# GMSL_SERIALIZER.net
KiCad netlist of a schematic drawn in Altium Designer
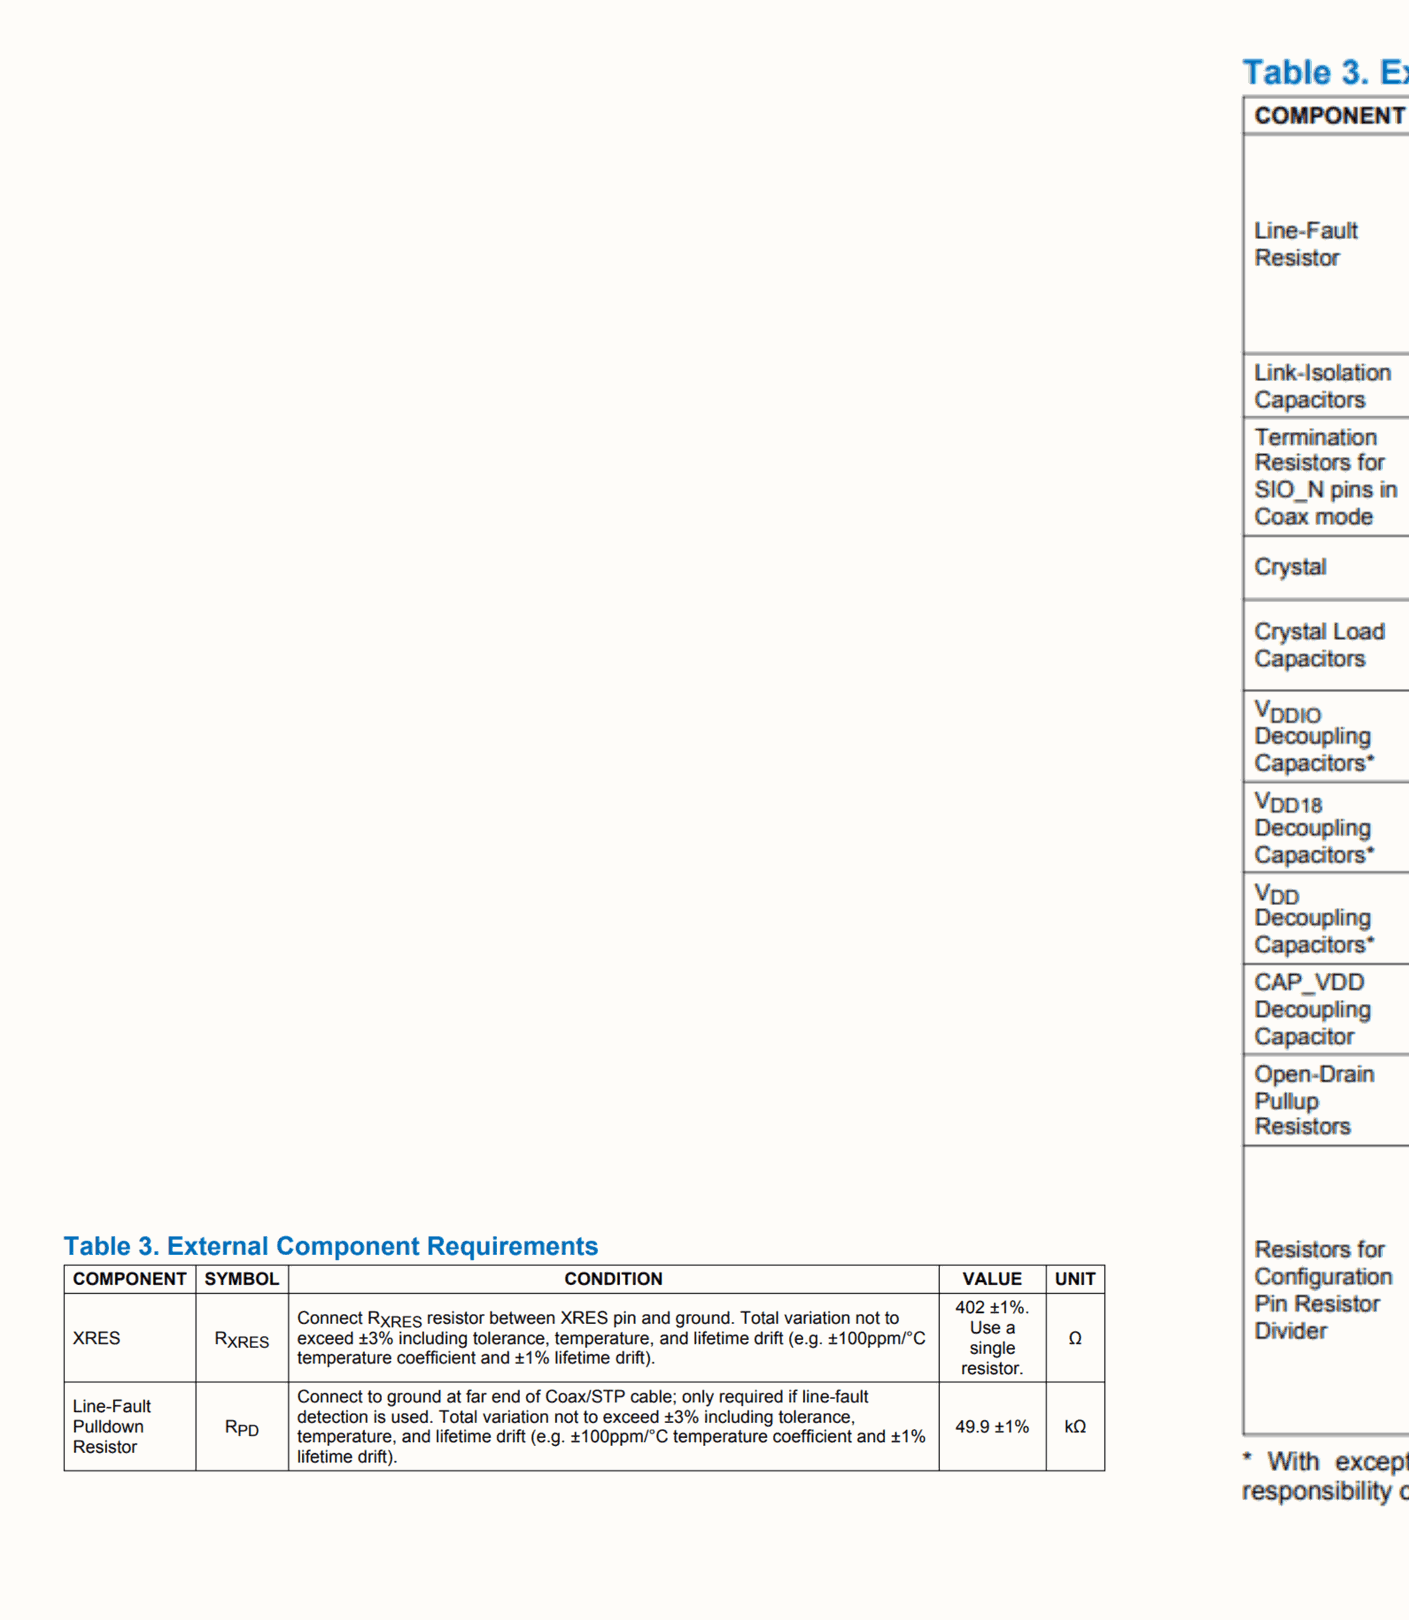
[diagram p0: GMSL_SERIALIZER.SchDoc, top left]
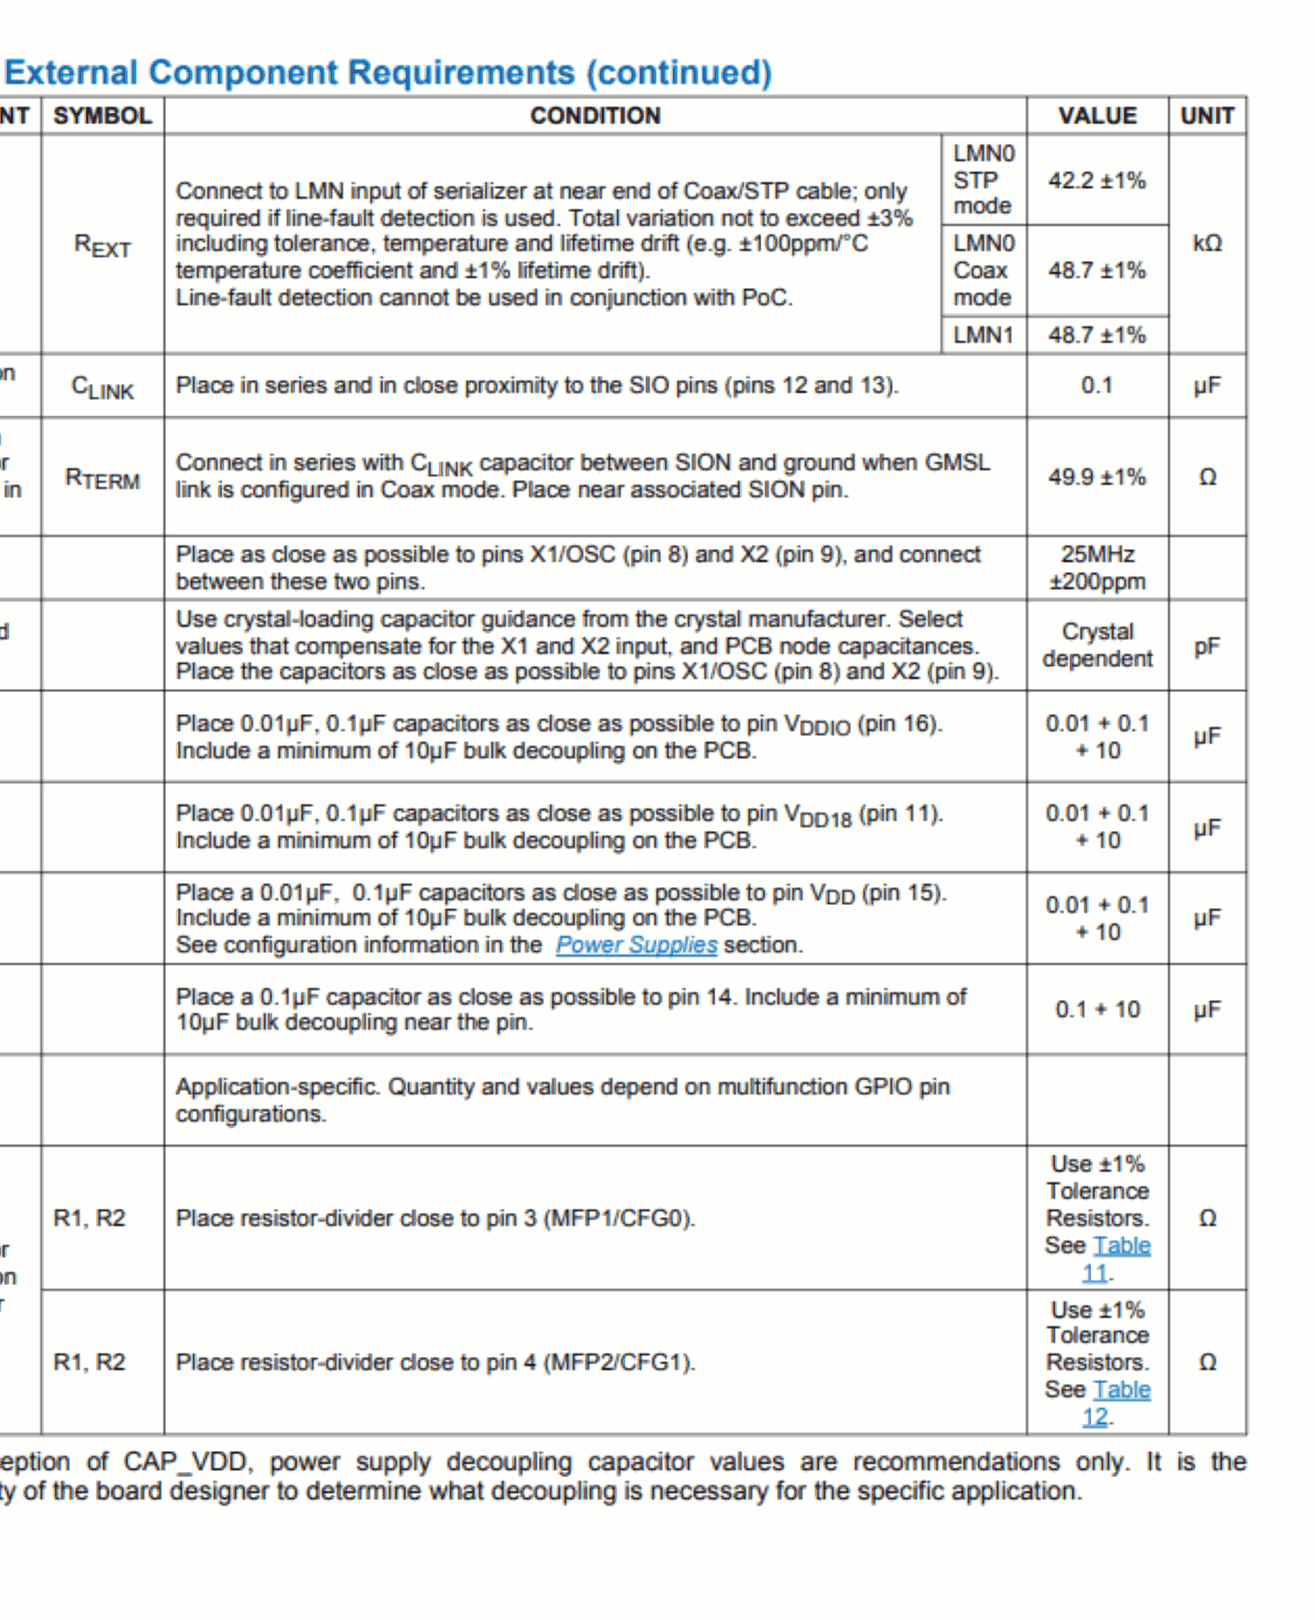
[diagram p1: GMSL_SERIALIZER.SchDoc, top right]
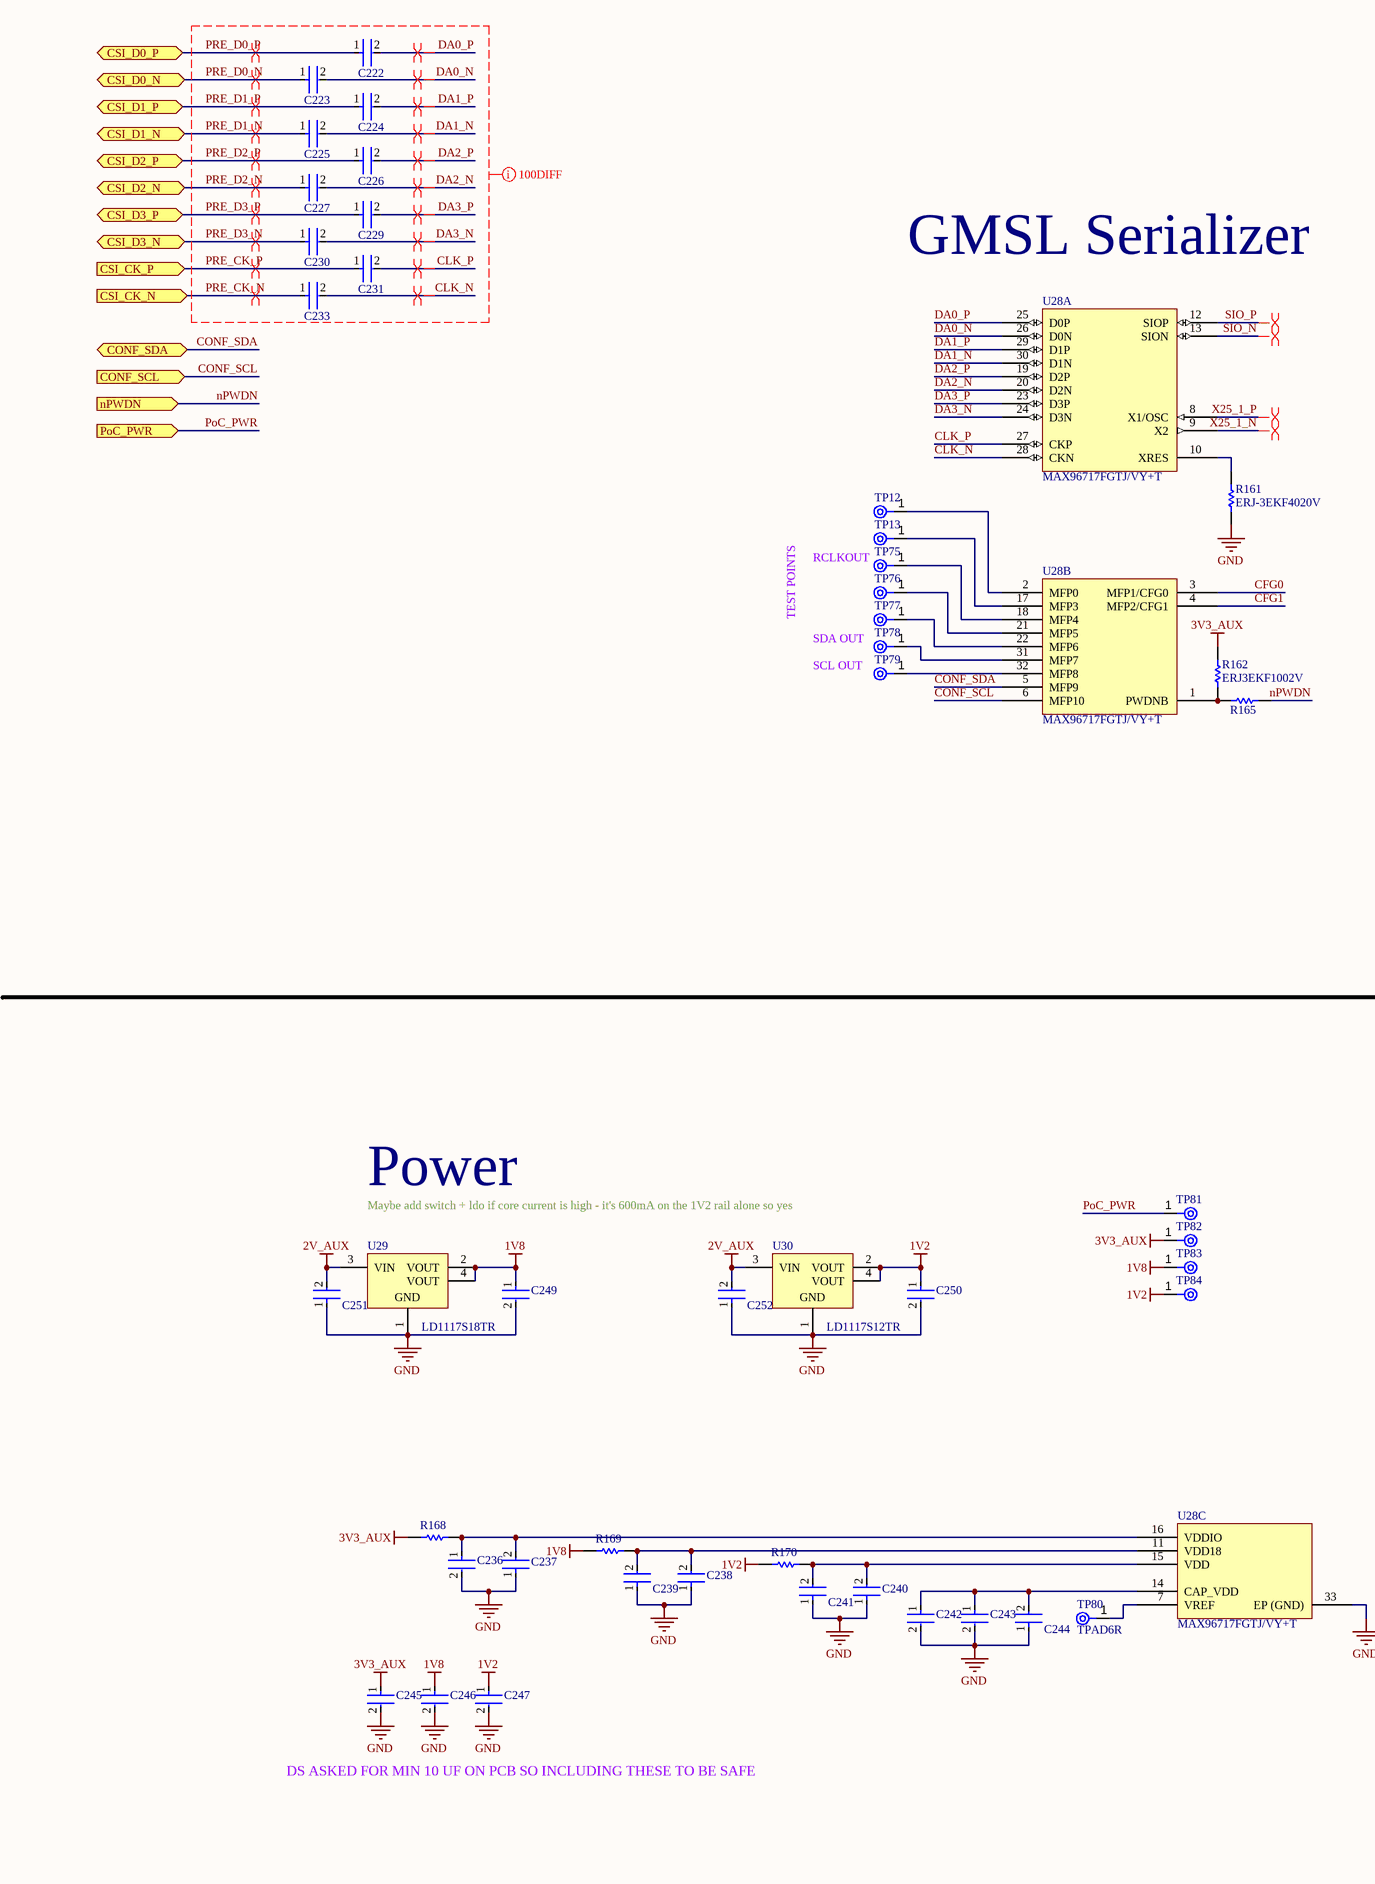
[diagram p2: GMSL_SERIALIZER.SchDoc, bottom left]
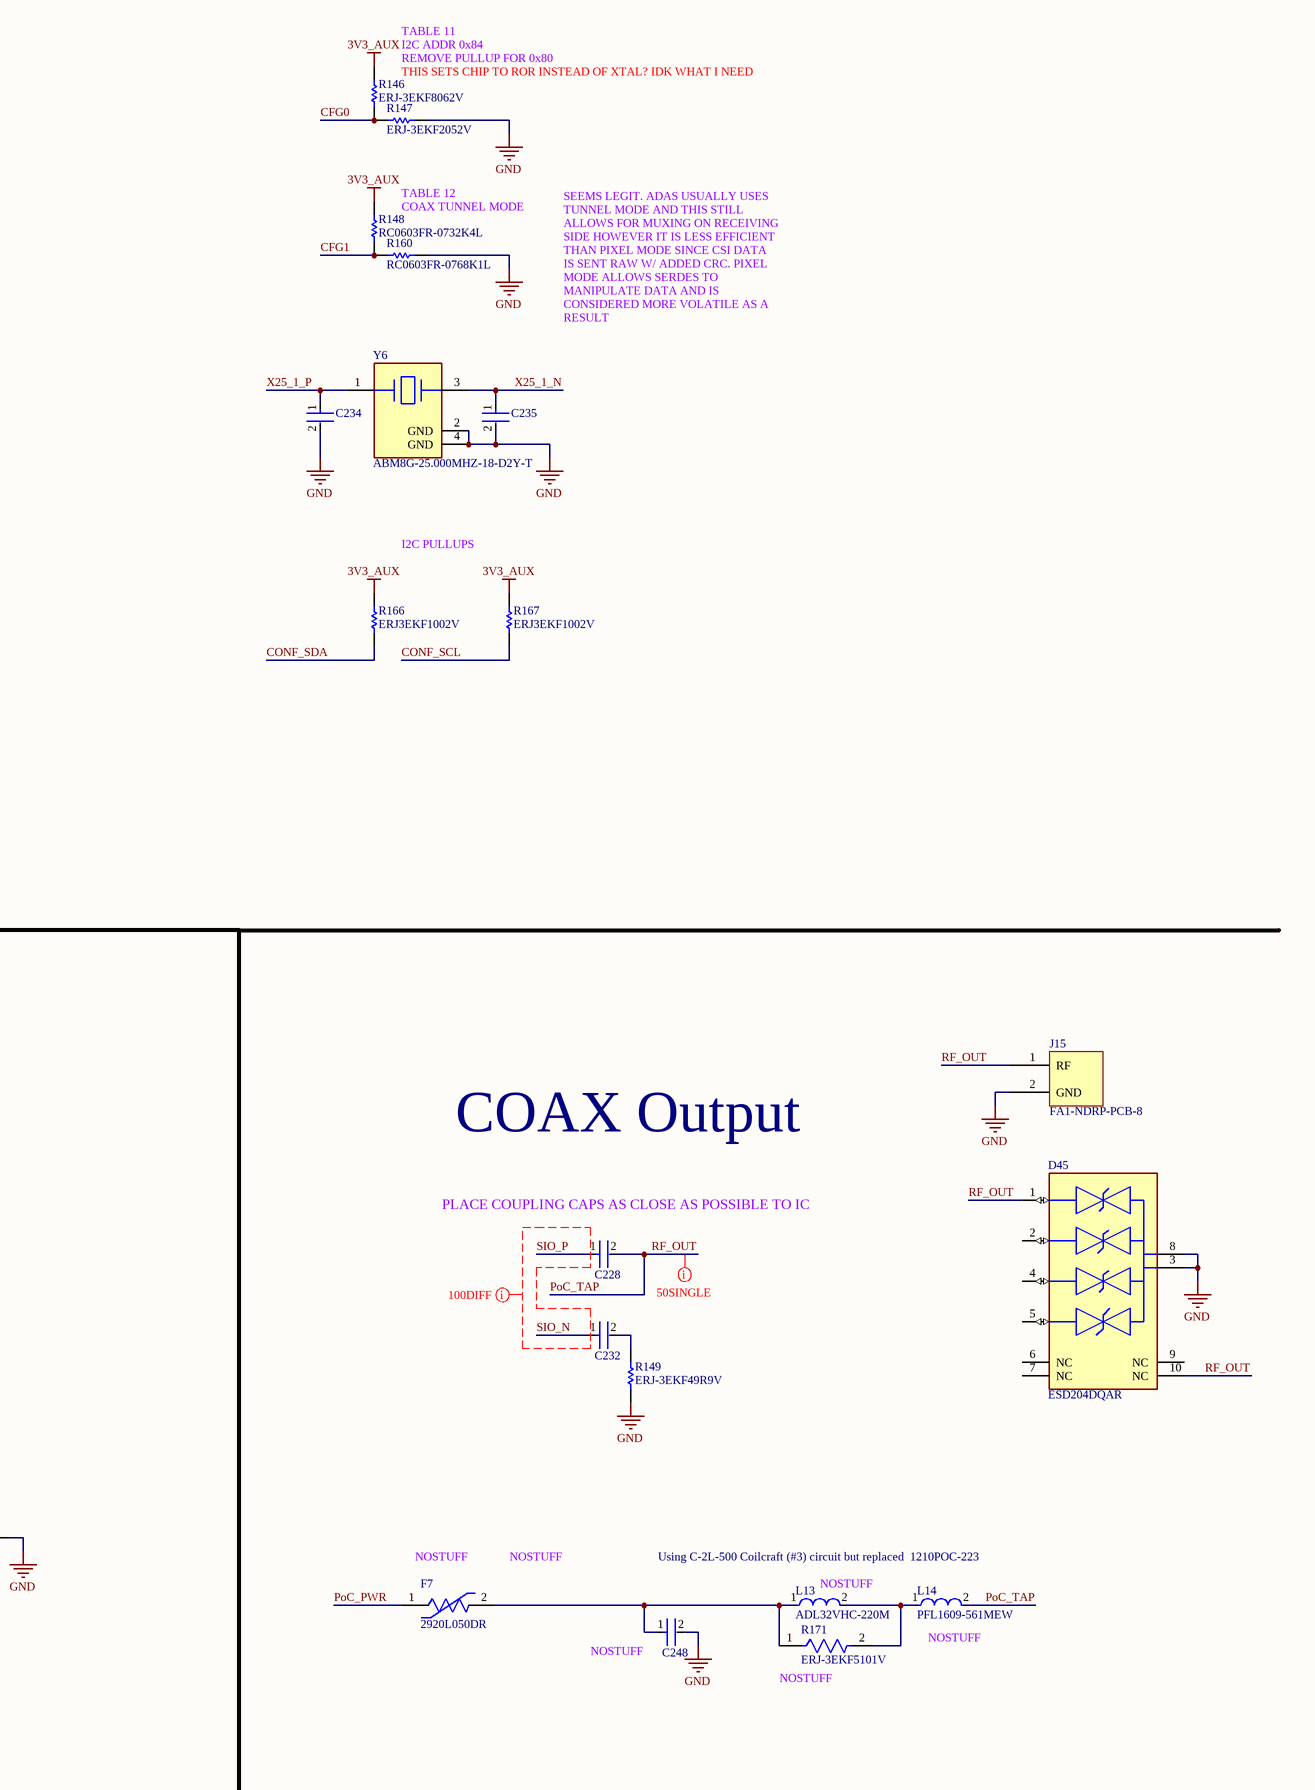
[diagram p3: GMSL_SERIALIZER.SchDoc, bottom right]

(export (version "E")
  (design (tool "Eeschema 10.0.6"))
  (components
    (comp (ref "C222")
      (value "C1005X7R1H104K050BB")
      (footprint "FP-C1005-050-0_05-IPC_C")
      (description "Multilayer Ceramic Capacitors 100nF ±10% 50V X7R SMD 0402")
      (fields (field (name "VOLTAGE") "50V") (field (name "TOLERANCE") "10%"))
      (libsource (lib "Altium Content Vault") (part "b4654b650e69147ec39a6b967a45e02"))
    )
    (comp (ref "C223")
      (value "C1005X7R1H104K050BB")
      (footprint "FP-C1005-050-0_05-IPC_C")
      (description "Multilayer Ceramic Capacitors 100nF ±10% 50V X7R SMD 0402")
      (fields (field (name "VOLTAGE") "50V") (field (name "TOLERANCE") "10%"))
      (libsource (lib "Altium Content Vault") (part "b4654b650e69147ec39a6b967a45e02"))
    )
    (comp (ref "C224")
      (value "C1005X7R1H104K050BB")
      (footprint "FP-C1005-050-0_05-IPC_C")
      (description "Multilayer Ceramic Capacitors 100nF ±10% 50V X7R SMD 0402")
      (fields (field (name "VOLTAGE") "50V") (field (name "TOLERANCE") "10%"))
      (libsource (lib "Altium Content Vault") (part "b4654b650e69147ec39a6b967a45e02"))
    )
    (comp (ref "C225")
      (value "C1005X7R1H104K050BB")
      (footprint "FP-C1005-050-0_05-IPC_C")
      (description "Multilayer Ceramic Capacitors 100nF ±10% 50V X7R SMD 0402")
      (fields (field (name "VOLTAGE") "50V") (field (name "TOLERANCE") "10%"))
      (libsource (lib "Altium Content Vault") (part "b4654b650e69147ec39a6b967a45e02"))
    )
    (comp (ref "C226")
      (value "C1005X7R1H104K050BB")
      (footprint "FP-C1005-050-0_05-IPC_C")
      (description "Multilayer Ceramic Capacitors 100nF ±10% 50V X7R SMD 0402")
      (fields (field (name "VOLTAGE") "50V") (field (name "TOLERANCE") "10%"))
      (libsource (lib "Altium Content Vault") (part "b4654b650e69147ec39a6b967a45e02"))
    )
    (comp (ref "C227")
      (value "C1005X7R1H104K050BB")
      (footprint "FP-C1005-050-0_05-IPC_C")
      (description "Multilayer Ceramic Capacitors 100nF ±10% 50V X7R SMD 0402")
      (fields (field (name "VOLTAGE") "50V") (field (name "TOLERANCE") "10%"))
      (libsource (lib "Altium Content Vault") (part "b4654b650e69147ec39a6b967a45e02"))
    )
    (comp (ref "C228")
      (value "C1005X7R1H104K050BB")
      (footprint "FP-C1005-050-0_05-IPC_C")
      (description "Multilayer Ceramic Capacitors 100nF ±10% 50V X7R SMD 0402")
      (fields (field (name "VOLTAGE") "50V") (field (name "TOLERANCE") "10%"))
      (libsource (lib "Altium Content Vault") (part "b4654b650e69147ec39a6b967a45e02"))
    )
    (comp (ref "C229")
      (value "C1005X7R1H104K050BB")
      (footprint "FP-C1005-050-0_05-IPC_C")
      (description "Multilayer Ceramic Capacitors 100nF ±10% 50V X7R SMD 0402")
      (fields (field (name "VOLTAGE") "50V") (field (name "TOLERANCE") "10%"))
      (libsource (lib "Altium Content Vault") (part "b4654b650e69147ec39a6b967a45e02"))
    )
    (comp (ref "C230")
      (value "C1005X7R1H104K050BB")
      (footprint "FP-C1005-050-0_05-IPC_C")
      (description "Multilayer Ceramic Capacitors 100nF ±10% 50V X7R SMD 0402")
      (fields (field (name "VOLTAGE") "50V") (field (name "TOLERANCE") "10%"))
      (libsource (lib "Altium Content Vault") (part "b4654b650e69147ec39a6b967a45e02"))
    )
    (comp (ref "C231")
      (value "C1005X7R1H104K050BB")
      (footprint "FP-C1005-050-0_05-IPC_C")
      (description "Multilayer Ceramic Capacitors 100nF ±10% 50V X7R SMD 0402")
      (fields (field (name "VOLTAGE") "50V") (field (name "TOLERANCE") "10%"))
      (libsource (lib "Altium Content Vault") (part "b4654b650e69147ec39a6b967a45e02"))
    )
    (comp (ref "C232")
      (value "C1005X7R1H104K050BB")
      (footprint "FP-C1005-050-0_05-IPC_C")
      (description "Multilayer Ceramic Capacitors 100nF ±10% 50V X7R SMD 0402")
      (fields (field (name "VOLTAGE") "50V") (field (name "TOLERANCE") "10%"))
      (libsource (lib "Altium Content Vault") (part "b4654b650e69147ec39a6b967a45e02"))
    )
    (comp (ref "C233")
      (value "C1005X7R1H104K050BB")
      (footprint "FP-C1005-050-0_05-IPC_C")
      (description "Multilayer Ceramic Capacitors 100nF ±10% 50V X7R SMD 0402")
      (fields (field (name "VOLTAGE") "50V") (field (name "TOLERANCE") "10%"))
      (libsource (lib "Altium Content Vault") (part "b4654b650e69147ec39a6b967a45e02"))
    )
    (comp (ref "C234")
      (value "C0603C300J5GACTU")
      (footprint "FP-C0603C-CF-MFG")
      (description "CAP CER 30PF 50V 5% NP0 0603")
      (fields
        (field (name "MANUFACTURER") "KEMET")
        (field (name "OCTOPART") "https://octopart.com/c0603c300j5gactu-kemet-199455")
      )
      (libsource (lib "Altium Content Vault") (part "b4654b650e69147ec39a6b967a45e02"))
    )
    (comp (ref "C235")
      (value "C0603C300J5GACTU")
      (footprint "FP-C0603C-CF-MFG")
      (description "CAP CER 30PF 50V 5% NP0 0603")
      (fields
        (field (name "MANUFACTURER") "KEMET")
        (field (name "OCTOPART") "https://octopart.com/c0603c300j5gactu-kemet-199455")
      )
      (libsource (lib "Altium Content Vault") (part "b4654b650e69147ec39a6b967a45e02"))
    )
    (comp (ref "C236")
      (value "CL05A106MP5NUNC")
      (footprint "FP-CL05A106MP5NUNC-MFG")
      (description "CAP CER 10UF 10V X5R 0402")
      (fields
        (field (name "OCTOPART") "https://octopart.com/cl05a106mp5nunc-samsung-22457395")
        (field (name "TOLERANCE") "20%")
      )
      (libsource (lib "Altium Content Vault") (part "b4654b650e69147ec39a6b967a45e02"))
    )
    (comp (ref "C237")
      (value "C0402C103M5RACTU")
      (footprint "FP-C0402-BB-MFG")
      (description "CAP CER 10000PF 50V 20% X7R 0402")
      (fields
        (field (name "TOLERANCE") "0.2")
        (field (name "OCTOPART") "https://octopart.com/c0402c103m5ractu-kemet-17125571")
      )
      (libsource (lib "Altium Content Vault") (part "b4654b650e69147ec39a6b967a45e02"))
    )
    (comp (ref "C238")
      (value "C0402C103M5RACTU")
      (footprint "FP-C0402-BB-MFG")
      (description "CAP CER 10000PF 50V 20% X7R 0402")
      (fields
        (field (name "TOLERANCE") "0.2")
        (field (name "OCTOPART") "https://octopart.com/c0402c103m5ractu-kemet-17125571")
      )
      (libsource (lib "Altium Content Vault") (part "b4654b650e69147ec39a6b967a45e02"))
    )
    (comp (ref "C239")
      (value "C1005X7R1H104K050BB")
      (footprint "FP-C1005-050-0_05-IPC_C")
      (description "Multilayer Ceramic Capacitors 100nF ±10% 50V X7R SMD 0402")
      (fields (field (name "VOLTAGE") "50V") (field (name "TOLERANCE") "10%"))
      (libsource (lib "Altium Content Vault") (part "b4654b650e69147ec39a6b967a45e02"))
    )
    (comp (ref "C240")
      (value "C0402C103M5RACTU")
      (footprint "FP-C0402-BB-MFG")
      (description "CAP CER 10000PF 50V 20% X7R 0402")
      (fields
        (field (name "TOLERANCE") "0.2")
        (field (name "OCTOPART") "https://octopart.com/c0402c103m5ractu-kemet-17125571")
      )
      (libsource (lib "Altium Content Vault") (part "b4654b650e69147ec39a6b967a45e02"))
    )
    (comp (ref "C241")
      (value "C1005X7R1H104K050BB")
      (footprint "FP-C1005-050-0_05-IPC_C")
      (description "Multilayer Ceramic Capacitors 100nF ±10% 50V X7R SMD 0402")
      (fields (field (name "VOLTAGE") "50V") (field (name "TOLERANCE") "10%"))
      (libsource (lib "Altium Content Vault") (part "b4654b650e69147ec39a6b967a45e02"))
    )
    (comp (ref "C242")
      (value "CL05A106MP5NUNC")
      (footprint "FP-CL05A106MP5NUNC-MFG")
      (description "CAP CER 10UF 10V X5R 0402")
      (fields
        (field (name "OCTOPART") "https://octopart.com/cl05a106mp5nunc-samsung-22457395")
        (field (name "TOLERANCE") "20%")
      )
      (libsource (lib "Altium Content Vault") (part "b4654b650e69147ec39a6b967a45e02"))
    )
    (comp (ref "C243")
      (value "CL05A106MP5NUNC")
      (footprint "FP-CL05A106MP5NUNC-MFG")
      (description "CAP CER 10UF 10V X5R 0402")
      (fields
        (field (name "OCTOPART") "https://octopart.com/cl05a106mp5nunc-samsung-22457395")
        (field (name "TOLERANCE") "20%")
      )
      (libsource (lib "Altium Content Vault") (part "b4654b650e69147ec39a6b967a45e02"))
    )
    (comp (ref "C244")
      (value "C1005X7R1H104K050BB")
      (footprint "FP-C1005-050-0_05-IPC_C")
      (description "Multilayer Ceramic Capacitors 100nF ±10% 50V X7R SMD 0402")
      (fields (field (name "VOLTAGE") "50V") (field (name "TOLERANCE") "10%"))
      (libsource (lib "Altium Content Vault") (part "b4654b650e69147ec39a6b967a45e02"))
    )
    (comp (ref "C245")
      (value "CL05A106MP5NUNC")
      (footprint "FP-CL05A106MP5NUNC-MFG")
      (description "CAP CER 10UF 10V X5R 0402")
      (fields
        (field (name "OCTOPART") "https://octopart.com/cl05a106mp5nunc-samsung-22457395")
        (field (name "TOLERANCE") "20%")
      )
      (libsource (lib "Altium Content Vault") (part "b4654b650e69147ec39a6b967a45e02"))
    )
    (comp (ref "C246")
      (value "CL05A106MP5NUNC")
      (footprint "FP-CL05A106MP5NUNC-MFG")
      (description "CAP CER 10UF 10V X5R 0402")
      (fields
        (field (name "OCTOPART") "https://octopart.com/cl05a106mp5nunc-samsung-22457395")
        (field (name "TOLERANCE") "20%")
      )
      (libsource (lib "Altium Content Vault") (part "b4654b650e69147ec39a6b967a45e02"))
    )
    (comp (ref "C247")
      (value "CL05A106MP5NUNC")
      (footprint "FP-CL05A106MP5NUNC-MFG")
      (description "CAP CER 10UF 10V X5R 0402")
      (fields
        (field (name "OCTOPART") "https://octopart.com/cl05a106mp5nunc-samsung-22457395")
        (field (name "TOLERANCE") "20%")
      )
      (libsource (lib "Altium Content Vault") (part "b4654b650e69147ec39a6b967a45e02"))
    )
    (comp (ref "C248")
      (value "GRM21BR61E226ME44L")
      (footprint "FP-GRM21B-0_2-e0_2_0_7-IPC_B")
      (description "Chip Multilayer Ceramic Capacitors for General Purpose, 0805, 22uF, X5R, 15%, 20%, 25V")
      (fields (field (name "TOLERANCE") "20%") (field (name "VOLTAGE") "25V"))
      (libsource (lib "Altium Content Vault") (part "b4654b650e69147ec39a6b967a45e02"))
    )
    (comp (ref "C249")
      (value "GRM188R60J106ME47D")
      (footprint "FP-GRM188-0_1-e0_2_0_55-IPC_A")
      (description "Chip Multilayer Ceramic Capacitors for General Purpose, 0603, 10uF, X5R, 15%, 20%, 6.3V")
      (fields (field (name "VOLTAGE") "6.3V") (field (name "TOLERANCE") "20%"))
      (libsource (lib "Altium Content Vault") (part "02cd4be3c70576c341d710602a673aa"))
    )
    (comp (ref "C250")
      (value "GRM188R60J106ME47D")
      (footprint "FP-GRM188-0_1-e0_2_0_55-IPC_A")
      (description "Chip Multilayer Ceramic Capacitors for General Purpose, 0603, 10uF, X5R, 15%, 20%, 6.3V")
      (fields (field (name "VOLTAGE") "6.3V") (field (name "TOLERANCE") "20%"))
      (libsource (lib "Altium Content Vault") (part "02cd4be3c70576c341d710602a673aa"))
    )
    (comp (ref "C251")
      (value "C1005X7R1H104K050BB")
      (footprint "FP-C1005-050-0_05-IPC_C")
      (description "Multilayer Ceramic Capacitors 100nF ±10% 50V X7R SMD 0402")
      (fields (field (name "VOLTAGE") "50V") (field (name "TOLERANCE") "10%"))
      (libsource (lib "Altium Content Vault") (part "b4654b650e69147ec39a6b967a45e02"))
    )
    (comp (ref "C252")
      (value "C1005X7R1H104K050BB")
      (footprint "FP-C1005-050-0_05-IPC_C")
      (description "Multilayer Ceramic Capacitors 100nF ±10% 50V X7R SMD 0402")
      (fields (field (name "VOLTAGE") "50V") (field (name "TOLERANCE") "10%"))
      (libsource (lib "Altium Content Vault") (part "b4654b650e69147ec39a6b967a45e02"))
    )
    (comp (ref "D45")
      (value "ESD204DQAR")
      (footprint "FP-DQA0010A-MFG")
      (description "4-CHANNEL LOW-CAPACITANCE SURGE")
      (fields
        (field (name "MANUFACTURER") "Texas Instruments")
        (field (name "OCTOPART") "https://octopart.com/esd204dqar-texas+instruments-89917476")
      )
      (libsource (lib "Altium Content Vault") (part "1465e58c1818c7767b55926832f0bf5"))
    )
    (comp (ref "F7")
      (value "2920L050DR")
      (footprint "FP-2920L050DR-MFG")
      (description "PTC RESET FUSE 60V 500MA 2920")
      (libsource (lib "Altium Content Vault") (part "1c6d77a0208143737455a0c7eb396be"))
    )
    (comp (ref "J15")
      (value "FA1-NDRP-PCB-8")
      (footprint "FA1-NDRP-PCB-8-Footprint-1")
      (description "RF F Connector, Male, Board Mount, Solder Terminal, Plug")
      (libsource (lib "Space Concordia") (part "FA1-NDRP-PCB-8"))
    )
    (comp (ref "L13")
      (value "ADL32VHC-220M")
      (footprint "FP-1210POC-MFG")
      (description "NOT COILCRAFT - ACTUAL P# --> ADL32VHC-220M\r\n - Power Injection Chokes for PoC")
      (fields
        (field (name "MANUFACTURER") "coilcraft")
        (field (name "OCTOPART") "https://octopart.com/1210poc-223mrc-coilcraft-103207315")
      )
      (libsource (lib "Altium Content Vault") (part "725321dda6339637d4d059423bc1c3c"))
    )
    (comp (ref "L14")
      (value "PFL1609-561MEW")
      (footprint "FP-PFL1609-MFG")
      (description "Fixed Inductors PFL1609 Low Profile 0.56 uH 20 % 1.4 A")
      (fields (field (name "MANUFACTURER") "coilcraft") (field (name "TOLERANCE") "20%"))
      (libsource (lib "Altium Content Vault") (part "725321dda6339637d4d059423bc1c3c"))
    )
    (comp (ref "R146")
      (value "ERJ-3EKF8062V")
      (footprint "RESC1608X55X30LL15T15")
      (fields (field (name "MANUFACTURER") "Panasonic"))
      (libsource (lib "Altium Content Vault") (part "RES"))
    )
    (comp (ref "R147")
      (value "ERJ-3EKF2052V")
      (footprint "RESC1608X55X30NL15T15")
      (fields (field (name "MANUFACTURER") "Panasonic"))
      (libsource (lib "Altium Content Vault") (part "RES"))
    )
    (comp (ref "R148")
      (value "RC0603FR-0732K4L")
      (footprint "RESC1608X55X25ML10T15")
      (fields (field (name "MANUFACTURER") "Yageo"))
      (libsource (lib "Altium Content Vault") (part "RES"))
    )
    (comp (ref "R149")
      (value "ERJ-3EKF49R9V")
      (footprint "RESC1608X55X30ML15T15")
      (fields (field (name "MANUFACTURER") "Panasonic"))
      (libsource (lib "Altium Content Vault") (part "RES"))
    )
    (comp (ref "R160")
      (value "RC0603FR-0768K1L")
      (footprint "RESC1608X55X25LL10T15")
      (fields (field (name "MANUFACTURER") "Yageo"))
      (libsource (lib "Altium Content Vault") (part "RES"))
    )
    (comp (ref "R161")
      (value "ERJ-3EKF4020V")
      (footprint "RESC1608X55X30LL15T15")
      (fields (field (name "MANUFACTURER") "Panasonic"))
      (libsource (lib "Altium Content Vault") (part "RES"))
    )
    (comp (ref "R162")
      (value "ERJ3EKF1002V")
      (footprint "RESC1609X55X30LL15T15")
      (description "Chip Resistor, 10 KOhm, +/- 1%, 0.1 W, -55 to 155 degC, 0603 (1608 Metric), RoHS, Tape and Reel")
      (fields (field (name "TOLERANCE") "1%") (field (name "MANUFACTURER") "Panasonic"))
      (libsource (lib "Altium Content Vault") (part "RES-2"))
    )
    (comp (ref "R165")
      (value "0402 JUMPER")
      (footprint "RESC1005X40X25ML05T05")
      (description "READ THE NAME")
      (libsource (lib "Space Concordia") (part "CMP-009-00206-2"))
    )
    (comp (ref "R166")
      (value "ERJ3EKF1002V")
      (footprint "RESC1609X55X30LL15T15")
      (description "Chip Resistor, 10 KOhm, +/- 1%, 0.1 W, -55 to 155 degC, 0603 (1608 Metric), RoHS, Tape and Reel")
      (fields (field (name "TOLERANCE") "1%") (field (name "MANUFACTURER") "Panasonic"))
      (libsource (lib "Altium Content Vault") (part "RES-2"))
    )
    (comp (ref "R167")
      (value "ERJ3EKF1002V")
      (footprint "RESC1609X55X30LL15T15")
      (description "Chip Resistor, 10 KOhm, +/- 1%, 0.1 W, -55 to 155 degC, 0603 (1608 Metric), RoHS, Tape and Reel")
      (fields (field (name "TOLERANCE") "1%") (field (name "MANUFACTURER") "Panasonic"))
      (libsource (lib "Altium Content Vault") (part "RES-2"))
    )
    (comp (ref "R168")
      (value "RC0402JR-070RL")
      (footprint "RESC1005X40X25NL05T10")
      (fields (field (name "MANUFACTURER") "Yageo / Phycomp"))
      (libsource (lib "Altium Content Vault") (part "RES"))
    )
    (comp (ref "R169")
      (value "RC0402JR-070RL")
      (footprint "RESC1005X40X25NL05T10")
      (fields (field (name "MANUFACTURER") "Yageo / Phycomp"))
      (libsource (lib "Altium Content Vault") (part "RES"))
    )
    (comp (ref "R170")
      (value "RC0402JR-070RL")
      (footprint "RESC1005X40X25NL05T10")
      (fields (field (name "MANUFACTURER") "Yageo / Phycomp"))
      (libsource (lib "Altium Content Vault") (part "RES"))
    )
    (comp (ref "R171")
      (value "ERJ-3EKF5101V")
      (footprint "FP-ERJ3EK-MFG")
      (description "RES SMD 5.1K OHM 1% 1/10W 0603")
      (fields (field (name "TOLERANCE") "1%"))
      (libsource (lib "Altium Content Vault") (part "1029c3af85768c4190bb7ad29bc67b5"))
    )
    (comp (ref "TP12")
      (value "TPAD6R")
      (footprint "New footprint 1")
      (description "Test Point .6mm")
      (libsource (lib "Space Concordia") (part "TP"))
    )
    (comp (ref "TP13")
      (value "TPAD6R")
      (footprint "New footprint 1")
      (description "Test Point .6mm")
      (libsource (lib "Space Concordia") (part "TP"))
    )
    (comp (ref "TP75")
      (value "TPAD6R")
      (footprint "New footprint 1")
      (description "Test Point .6mm")
      (libsource (lib "Space Concordia") (part "TP"))
    )
    (comp (ref "TP76")
      (value "TPAD6R")
      (footprint "New footprint 1")
      (description "Test Point .6mm")
      (libsource (lib "Space Concordia") (part "TP"))
    )
    (comp (ref "TP77")
      (value "TPAD6R")
      (footprint "New footprint 1")
      (description "Test Point .6mm")
      (libsource (lib "Space Concordia") (part "TP"))
    )
    (comp (ref "TP78")
      (value "TPAD6R")
      (footprint "New footprint 1")
      (description "Test Point .6mm")
      (libsource (lib "Space Concordia") (part "TP"))
    )
    (comp (ref "TP79")
      (value "TPAD6R")
      (footprint "New footprint 1")
      (description "Test Point .6mm")
      (libsource (lib "Space Concordia") (part "TP"))
    )
    (comp (ref "TP80")
      (value "TPAD6R")
      (footprint "New footprint 1")
      (description "Test Point .6mm")
      (libsource (lib "Space Concordia") (part "TP"))
    )
    (comp (ref "TP81")
      (value "TPAD6R")
      (footprint "New footprint 1")
      (description "Test Point .6mm")
      (libsource (lib "Space Concordia") (part "TP"))
    )
    (comp (ref "TP82")
      (value "TPAD6R")
      (footprint "New footprint 1")
      (description "Test Point .6mm")
      (libsource (lib "Space Concordia") (part "TP"))
    )
    (comp (ref "TP83")
      (value "TPAD6R")
      (footprint "New footprint 1")
      (description "Test Point .6mm")
      (libsource (lib "Space Concordia") (part "TP"))
    )
    (comp (ref "TP84")
      (value "TPAD6R")
      (footprint "New footprint 1")
      (description "Test Point .6mm")
      (libsource (lib "Space Concordia") (part "TP"))
    )
    (comp (ref "U28")
      (value "MAX96717FGTJ/VY+T")
      (footprint "QFN50P500X500X80_HS-33N")
      (description "3Gbps Serializer TQFN-32 Serializers / Deserializers ROHS")
      (libsource (lib "Space Concordia") (part "MAX96717FGTJ_VY+T"))
    )
    (comp (ref "U29")
      (value "LD1117S18TR")
      (footprint "SOT-223_M")
      (description "Fixed Low Drop Positive Voltage Regulator, 1.8V, 4-Pin SOT-223, Tape and Reel")
      (libsource (lib "Altium Content Vault") (part "PM-REG-LD1117-SOT4"))
    )
    (comp (ref "U30")
      (value "LD1117S12TR")
      (footprint "SOT-223_M")
      (description "Fixed Low Drop Positive Voltage Regulator, 1.2V, 4-Pin SOT-223, Tape and Reel")
      (libsource (lib "Altium Content Vault") (part "PM-REG-LD1117-SOT4"))
    )
    (comp (ref "Y6")
      (value "ABM8G-25.000MHZ-18-D2Y-T")
      (footprint "FP-ABM8G-MFG")
      (description "Crystal 25MHz ±20ppm (Tol) ±30ppm (Stability) 18pF FUND 60Ω 4-Pin SMD T/R")
      (fields (field (name "TOLERANCE") "20ppm"))
      (libsource (lib "Altium Content Vault") (part "48e526d86b7f2615d98721063c72f49"))
    )
  )
  (nets
    (net (code "1") (name "/CFG0") (class "Default")
      (node (ref "R146") (pin "1") (pinfunction "1_1") (pintype "passive"))
      (node (ref "R147") (pin "2") (pinfunction "2_2") (pintype "passive"))
      (node (ref "U28") (pin "3") (pinfunction "MFP1/CFG0_3") (pintype "passive"))
    )
    (net (code "2") (name "/CFG1") (class "Default")
      (node (ref "R148") (pin "1") (pinfunction "1_1") (pintype "passive"))
      (node (ref "R160") (pin "2") (pinfunction "2_2") (pintype "passive"))
      (node (ref "U28") (pin "4") (pinfunction "MFP2/CFG1_4") (pintype "passive"))
    )
    (net (code "3") (name "/CLK_N") (class "Default")
      (node (ref "C233") (pin "2") (pinfunction "2_2") (pintype "passive"))
      (node (ref "U28") (pin "28") (pinfunction "CKN_28") (pintype "bidirectional"))
    )
    (net (code "4") (name "/CLK_P") (class "Default")
      (node (ref "C231") (pin "2") (pinfunction "2_2") (pintype "passive"))
      (node (ref "U28") (pin "27") (pinfunction "CKP_27") (pintype "bidirectional"))
    )
    (net (code "5") (name "/CONF_SCL") (class "Default")
      (node (ref "R167") (pin "1") (pinfunction "1_1") (pintype "passive"))
      (node (ref "U28") (pin "6") (pinfunction "MFP10_6") (pintype "passive"))
    )
    (net (code "6") (name "/CONF_SDA") (class "Default")
      (node (ref "R166") (pin "1") (pinfunction "1_1") (pintype "passive"))
      (node (ref "U28") (pin "5") (pinfunction "MFP9_5") (pintype "passive"))
    )
    (net (code "7") (name "/DA0_N") (class "Default")
      (node (ref "C223") (pin "2") (pinfunction "2_2") (pintype "passive"))
      (node (ref "U28") (pin "26") (pinfunction "D0N_26") (pintype "bidirectional"))
    )
    (net (code "8") (name "/DA0_P") (class "Default")
      (node (ref "C222") (pin "2") (pinfunction "2_2") (pintype "passive"))
      (node (ref "U28") (pin "25") (pinfunction "D0P_25") (pintype "bidirectional"))
    )
    (net (code "9") (name "/DA1_N") (class "Default")
      (node (ref "C225") (pin "2") (pinfunction "2_2") (pintype "passive"))
      (node (ref "U28") (pin "30") (pinfunction "D1N_30") (pintype "bidirectional"))
    )
    (net (code "10") (name "/DA1_P") (class "Default")
      (node (ref "C224") (pin "2") (pinfunction "2_2") (pintype "passive"))
      (node (ref "U28") (pin "29") (pinfunction "D1P_29") (pintype "bidirectional"))
    )
    (net (code "11") (name "/DA2_N") (class "Default")
      (node (ref "C227") (pin "2") (pinfunction "2_2") (pintype "passive"))
      (node (ref "U28") (pin "20") (pinfunction "D2N_20") (pintype "bidirectional"))
    )
    (net (code "12") (name "/DA2_P") (class "Default")
      (node (ref "C226") (pin "2") (pinfunction "2_2") (pintype "passive"))
      (node (ref "U28") (pin "19") (pinfunction "D2P_19") (pintype "bidirectional"))
    )
    (net (code "13") (name "/DA3_N") (class "Default")
      (node (ref "C230") (pin "2") (pinfunction "2_2") (pintype "passive"))
      (node (ref "U28") (pin "24") (pinfunction "D3N_24") (pintype "bidirectional"))
    )
    (net (code "14") (name "/DA3_P") (class "Default")
      (node (ref "C229") (pin "2") (pinfunction "2_2") (pintype "passive"))
      (node (ref "U28") (pin "23") (pinfunction "D3P_23") (pintype "bidirectional"))
    )
    (net (code "15") (name "/PRE_CK_N") (class "Default")
      (node (ref "C233") (pin "1") (pinfunction "1_1") (pintype "passive"))
    )
    (net (code "16") (name "/PRE_CK_P") (class "Default")
      (node (ref "C231") (pin "1") (pinfunction "1_1") (pintype "passive"))
    )
    (net (code "17") (name "/PRE_D0_N") (class "Default")
      (node (ref "C223") (pin "1") (pinfunction "1_1") (pintype "passive"))
    )
    (net (code "18") (name "/PRE_D0_P") (class "Default")
      (node (ref "C222") (pin "1") (pinfunction "1_1") (pintype "passive"))
    )
    (net (code "19") (name "/PRE_D1_N") (class "Default")
      (node (ref "C225") (pin "1") (pinfunction "1_1") (pintype "passive"))
    )
    (net (code "20") (name "/PRE_D1_P") (class "Default")
      (node (ref "C224") (pin "1") (pinfunction "1_1") (pintype "passive"))
    )
    (net (code "21") (name "/PRE_D2_N") (class "Default")
      (node (ref "C227") (pin "1") (pinfunction "1_1") (pintype "passive"))
    )
    (net (code "22") (name "/PRE_D2_P") (class "Default")
      (node (ref "C226") (pin "1") (pinfunction "1_1") (pintype "passive"))
    )
    (net (code "23") (name "/PRE_D3_N") (class "Default")
      (node (ref "C230") (pin "1") (pinfunction "1_1") (pintype "passive"))
    )
    (net (code "24") (name "/PRE_D3_P") (class "Default")
      (node (ref "C229") (pin "1") (pinfunction "1_1") (pintype "passive"))
    )
    (net (code "25") (name "/PoC_PWR") (class "Default")
      (node (ref "F7") (pin "1") (pinfunction "1_1") (pintype "passive"))
      (node (ref "TP81") (pin "1") (pinfunction "TP_1") (pintype "passive"))
    )
    (net (code "26") (name "/PoC_TAP") (class "Default")
      (node (ref "C228") (pin "2") (pinfunction "2_2") (pintype "passive"))
      (node (ref "D45") (pin "1") (pinfunction "IO1_1") (pintype "bidirectional"))
      (node (ref "D45") (pin "10") (pinfunction "NC_10") (pintype "passive"))
      (node (ref "J15") (pin "1") (pinfunction "RF_1") (pintype "passive"))
      (node (ref "L14") (pin "2") (pinfunction "2_2") (pintype "passive"))
    )
    (net (code "27") (name "/SIO_N") (class "Default")
      (node (ref "C232") (pin "1") (pinfunction "1_1") (pintype "passive"))
      (node (ref "U28") (pin "13") (pinfunction "SION_13") (pintype "bidirectional"))
    )
    (net (code "28") (name "/SIO_P") (class "Default")
      (node (ref "C228") (pin "1") (pinfunction "1_1") (pintype "passive"))
      (node (ref "U28") (pin "12") (pinfunction "SIOP_12") (pintype "bidirectional"))
    )
    (net (code "29") (name "/X25_1_N") (class "Default")
      (node (ref "C235") (pin "1") (pinfunction "1_1") (pintype "passive"))
      (node (ref "U28") (pin "9") (pinfunction "X2_9") (pintype "output"))
      (node (ref "Y6") (pin "3") (pinfunction "3_3") (pintype "passive"))
    )
    (net (code "30") (name "/X25_1_P") (class "Default")
      (node (ref "C234") (pin "1") (pinfunction "1_1") (pintype "passive"))
      (node (ref "U28") (pin "8") (pinfunction "X1/OSC_8") (pintype "input"))
      (node (ref "Y6") (pin "1") (pinfunction "1_1") (pintype "passive"))
    )
    (net (code "31") (name "/nPWDN") (class "Default")
      (node (ref "R165") (pin "2") (pinfunction "2_2") (pintype "passive"))
    )
    (net (code "32") (name "1V2") (class "Default")
      (node (ref "C247") (pin "1") (pinfunction "1_1") (pintype "passive"))
      (node (ref "C250") (pin "1") (pinfunction "1_1") (pintype "passive"))
      (node (ref "R170") (pin "1") (pinfunction "1_1") (pintype "passive"))
      (node (ref "TP84") (pin "1") (pinfunction "TP_1") (pintype "passive"))
      (node (ref "U30") (pin "2") (pinfunction "VOUT_2") (pintype "power_in"))
      (node (ref "U30") (pin "4") (pinfunction "VOUT_4") (pintype "power_in"))
    )
    (net (code "33") (name "1V8") (class "Default")
      (node (ref "C246") (pin "1") (pinfunction "1_1") (pintype "passive"))
      (node (ref "C249") (pin "1") (pinfunction "1_1") (pintype "passive"))
      (node (ref "R169") (pin "1") (pinfunction "1_1") (pintype "passive"))
      (node (ref "TP83") (pin "1") (pinfunction "TP_1") (pintype "passive"))
      (node (ref "U29") (pin "2") (pinfunction "VOUT_2") (pintype "power_in"))
      (node (ref "U29") (pin "4") (pinfunction "VOUT_4") (pintype "power_in"))
    )
    (net (code "34") (name "2V_AUX") (class "Default")
      (node (ref "C251") (pin "2") (pinfunction "2_2") (pintype "passive"))
      (node (ref "C252") (pin "2") (pinfunction "2_2") (pintype "passive"))
      (node (ref "U29") (pin "3") (pinfunction "VIN_3") (pintype "power_in"))
      (node (ref "U30") (pin "3") (pinfunction "VIN_3") (pintype "power_in"))
    )
    (net (code "35") (name "3V3_AUX") (class "Default")
      (node (ref "C245") (pin "1") (pinfunction "1_1") (pintype "passive"))
      (node (ref "R146") (pin "2") (pinfunction "2_2") (pintype "passive"))
      (node (ref "R148") (pin "2") (pinfunction "2_2") (pintype "passive"))
      (node (ref "R162") (pin "2") (pinfunction "2_2") (pintype "passive"))
      (node (ref "R166") (pin "2") (pinfunction "2_2") (pintype "passive"))
      (node (ref "R167") (pin "2") (pinfunction "2_2") (pintype "passive"))
      (node (ref "R168") (pin "1") (pinfunction "1_1") (pintype "passive"))
      (node (ref "TP82") (pin "1") (pinfunction "TP_1") (pintype "passive"))
    )
    (net (code "36") (name "GND") (class "Default")
      (node (ref "C234") (pin "2") (pinfunction "2_2") (pintype "passive"))
      (node (ref "C235") (pin "2") (pinfunction "2_2") (pintype "passive"))
      (node (ref "C236") (pin "2") (pinfunction "2_2") (pintype "passive"))
      (node (ref "C237") (pin "1") (pinfunction "1_1") (pintype "passive"))
      (node (ref "C238") (pin "1") (pinfunction "1_1") (pintype "passive"))
      (node (ref "C239") (pin "1") (pinfunction "1_1") (pintype "passive"))
      (node (ref "C240") (pin "1") (pinfunction "1_1") (pintype "passive"))
      (node (ref "C241") (pin "1") (pinfunction "1_1") (pintype "passive"))
      (node (ref "C242") (pin "2") (pinfunction "2_2") (pintype "passive"))
      (node (ref "C243") (pin "2") (pinfunction "2_2") (pintype "passive"))
      (node (ref "C244") (pin "1") (pinfunction "1_1") (pintype "passive"))
      (node (ref "C245") (pin "2") (pinfunction "2_2") (pintype "passive"))
      (node (ref "C246") (pin "2") (pinfunction "2_2") (pintype "passive"))
      (node (ref "C247") (pin "2") (pinfunction "2_2") (pintype "passive"))
      (node (ref "C248") (pin "2") (pinfunction "2_2") (pintype "passive"))
      (node (ref "C249") (pin "2") (pinfunction "2_2") (pintype "passive"))
      (node (ref "C250") (pin "2") (pinfunction "2_2") (pintype "passive"))
      (node (ref "C251") (pin "1") (pinfunction "1_1") (pintype "passive"))
      (node (ref "C252") (pin "1") (pinfunction "1_1") (pintype "passive"))
      (node (ref "D45") (pin "3") (pinfunction "GND_3") (pintype "power_in"))
      (node (ref "D45") (pin "8") (pinfunction "GND_8") (pintype "power_in"))
      (node (ref "J15") (pin "2") (pinfunction "GND_2") (pintype "passive"))
      (node (ref "R147") (pin "1") (pinfunction "1_1") (pintype "passive"))
      (node (ref "R149") (pin "1") (pinfunction "1_1") (pintype "passive"))
      (node (ref "R160") (pin "1") (pinfunction "1_1") (pintype "passive"))
      (node (ref "R161") (pin "1") (pinfunction "1_1") (pintype "passive"))
      (node (ref "U28") (pin "33") (pinfunction "EP_(GND)_33") (pintype "power_in"))
      (node (ref "U29") (pin "1") (pinfunction "GND_1") (pintype "power_in"))
      (node (ref "U30") (pin "1") (pinfunction "GND_1") (pintype "power_in"))
      (node (ref "Y6") (pin "2") (pinfunction "GND_2") (pintype "power_in"))
      (node (ref "Y6") (pin "4") (pinfunction "GND_4") (pintype "power_in"))
    )
    (net (code "37") (name "Net-(C232-Pad2)") (class "Default")
      (node (ref "C232") (pin "2") (pinfunction "2_2") (pintype "passive"))
      (node (ref "R149") (pin "2") (pinfunction "2_2") (pintype "passive"))
    )
    (net (code "38") (name "Net-(C248-Pad1)") (class "Default")
      (node (ref "C248") (pin "1") (pinfunction "1_1") (pintype "passive"))
      (node (ref "F7") (pin "2") (pinfunction "2_2") (pintype "passive"))
      (node (ref "L13") (pin "1") (pinfunction "1_1") (pintype "passive"))
      (node (ref "R171") (pin "1") (pinfunction "1_1") (pintype "passive"))
    )
    (net (code "39") (name "Net-(L13-Pad2)") (class "Default")
      (node (ref "L13") (pin "2") (pinfunction "2_2") (pintype "passive"))
      (node (ref "L14") (pin "1") (pinfunction "1_1") (pintype "passive"))
      (node (ref "R171") (pin "2") (pinfunction "2_2") (pintype "passive"))
    )
    (net (code "40") (name "Net-(TP12-TP)") (class "Default")
      (node (ref "TP12") (pin "1") (pinfunction "TP_1") (pintype "passive"))
      (node (ref "U28") (pin "2") (pinfunction "MFP0_2") (pintype "passive"))
    )
    (net (code "41") (name "Net-(TP13-TP)") (class "Default")
      (node (ref "TP13") (pin "1") (pinfunction "TP_1") (pintype "passive"))
      (node (ref "U28") (pin "17") (pinfunction "MFP3_17") (pintype "passive"))
    )
    (net (code "42") (name "Net-(TP75-TP)") (class "Default")
      (node (ref "TP75") (pin "1") (pinfunction "TP_1") (pintype "passive"))
      (node (ref "U28") (pin "18") (pinfunction "MFP4_18") (pintype "passive"))
    )
    (net (code "43") (name "Net-(TP76-TP)") (class "Default")
      (node (ref "TP76") (pin "1") (pinfunction "TP_1") (pintype "passive"))
      (node (ref "U28") (pin "21") (pinfunction "MFP5_21") (pintype "passive"))
    )
    (net (code "44") (name "Net-(TP77-TP)") (class "Default")
      (node (ref "TP77") (pin "1") (pinfunction "TP_1") (pintype "passive"))
      (node (ref "U28") (pin "22") (pinfunction "MFP6_22") (pintype "passive"))
    )
    (net (code "45") (name "Net-(TP78-TP)") (class "Default")
      (node (ref "TP78") (pin "1") (pinfunction "TP_1") (pintype "passive"))
      (node (ref "U28") (pin "31") (pinfunction "MFP7_31") (pintype "passive"))
    )
    (net (code "46") (name "Net-(TP79-TP)") (class "Default")
      (node (ref "TP79") (pin "1") (pinfunction "TP_1") (pintype "passive"))
      (node (ref "U28") (pin "32") (pinfunction "MFP8_32") (pintype "passive"))
    )
    (net (code "47") (name "Net-(TP80-TP)") (class "Default")
      (node (ref "TP80") (pin "1") (pinfunction "TP_1") (pintype "passive"))
      (node (ref "U28") (pin "7") (pinfunction "VREF_7") (pintype "power_in"))
    )
    (net (code "48") (name "Net-(U28A-XRES)") (class "Default")
      (node (ref "R161") (pin "2") (pinfunction "2_2") (pintype "passive"))
      (node (ref "U28") (pin "10") (pinfunction "XRES_10") (pintype "passive"))
    )
    (net (code "49") (name "Net-(U28B-PWDNB)") (class "Default")
      (node (ref "R162") (pin "1") (pinfunction "1_1") (pintype "passive"))
      (node (ref "R165") (pin "1") (pinfunction "1_1") (pintype "passive"))
      (node (ref "U28") (pin "1") (pinfunction "PWDNB_1") (pintype "passive"))
    )
    (net (code "50") (name "Net-(U28C-CAP_VDD)") (class "Default")
      (node (ref "C242") (pin "1") (pinfunction "1_1") (pintype "passive"))
      (node (ref "C243") (pin "1") (pinfunction "1_1") (pintype "passive"))
      (node (ref "C244") (pin "2") (pinfunction "2_2") (pintype "passive"))
      (node (ref "U28") (pin "14") (pinfunction "CAP_VDD_14") (pintype "power_in"))
    )
    (net (code "51") (name "Net-(U28C-VDD)") (class "Default")
      (node (ref "C240") (pin "2") (pinfunction "2_2") (pintype "passive"))
      (node (ref "C241") (pin "2") (pinfunction "2_2") (pintype "passive"))
      (node (ref "R170") (pin "2") (pinfunction "2_2") (pintype "passive"))
      (node (ref "U28") (pin "15") (pinfunction "VDD_15") (pintype "power_in"))
    )
    (net (code "52") (name "Net-(U28C-VDD18)") (class "Default")
      (node (ref "C238") (pin "2") (pinfunction "2_2") (pintype "passive"))
      (node (ref "C239") (pin "2") (pinfunction "2_2") (pintype "passive"))
      (node (ref "R169") (pin "2") (pinfunction "2_2") (pintype "passive"))
      (node (ref "U28") (pin "11") (pinfunction "VDD18_11") (pintype "power_in"))
    )
    (net (code "53") (name "Net-(U28C-VDDIO)") (class "Default")
      (node (ref "C236") (pin "1") (pinfunction "1_1") (pintype "passive"))
      (node (ref "C237") (pin "2") (pinfunction "2_2") (pintype "passive"))
      (node (ref "R168") (pin "2") (pinfunction "2_2") (pintype "passive"))
      (node (ref "U28") (pin "16") (pinfunction "VDDIO_16") (pintype "power_in"))
    )
    (net (code "54") (name "unconnected-(D45-IO2-Pad2)") (class "Default")
      (node (ref "D45") (pin "2") (pinfunction "IO2_2") (pintype "bidirectional"))
    )
    (net (code "55") (name "unconnected-(D45-IO3-Pad4)") (class "Default")
      (node (ref "D45") (pin "4") (pinfunction "IO3_4") (pintype "bidirectional"))
    )
    (net (code "56") (name "unconnected-(D45-IO4-Pad5)") (class "Default")
      (node (ref "D45") (pin "5") (pinfunction "IO4_5") (pintype "bidirectional"))
    )
    (net (code "57") (name "unconnected-(D45-NC-Pad6)") (class "Default")
      (node (ref "D45") (pin "6") (pinfunction "NC_6") (pintype "passive"))
    )
    (net (code "58") (name "unconnected-(D45-NC-Pad7)") (class "Default")
      (node (ref "D45") (pin "7") (pinfunction "NC_7") (pintype "passive"))
    )
    (net (code "59") (name "unconnected-(D45-NC-Pad9)") (class "Default")
      (node (ref "D45") (pin "9") (pinfunction "NC_9") (pintype "passive"))
    )
  )
)
